# XBee4.net
KiCad netlist of a schematic drawn in EAGLE
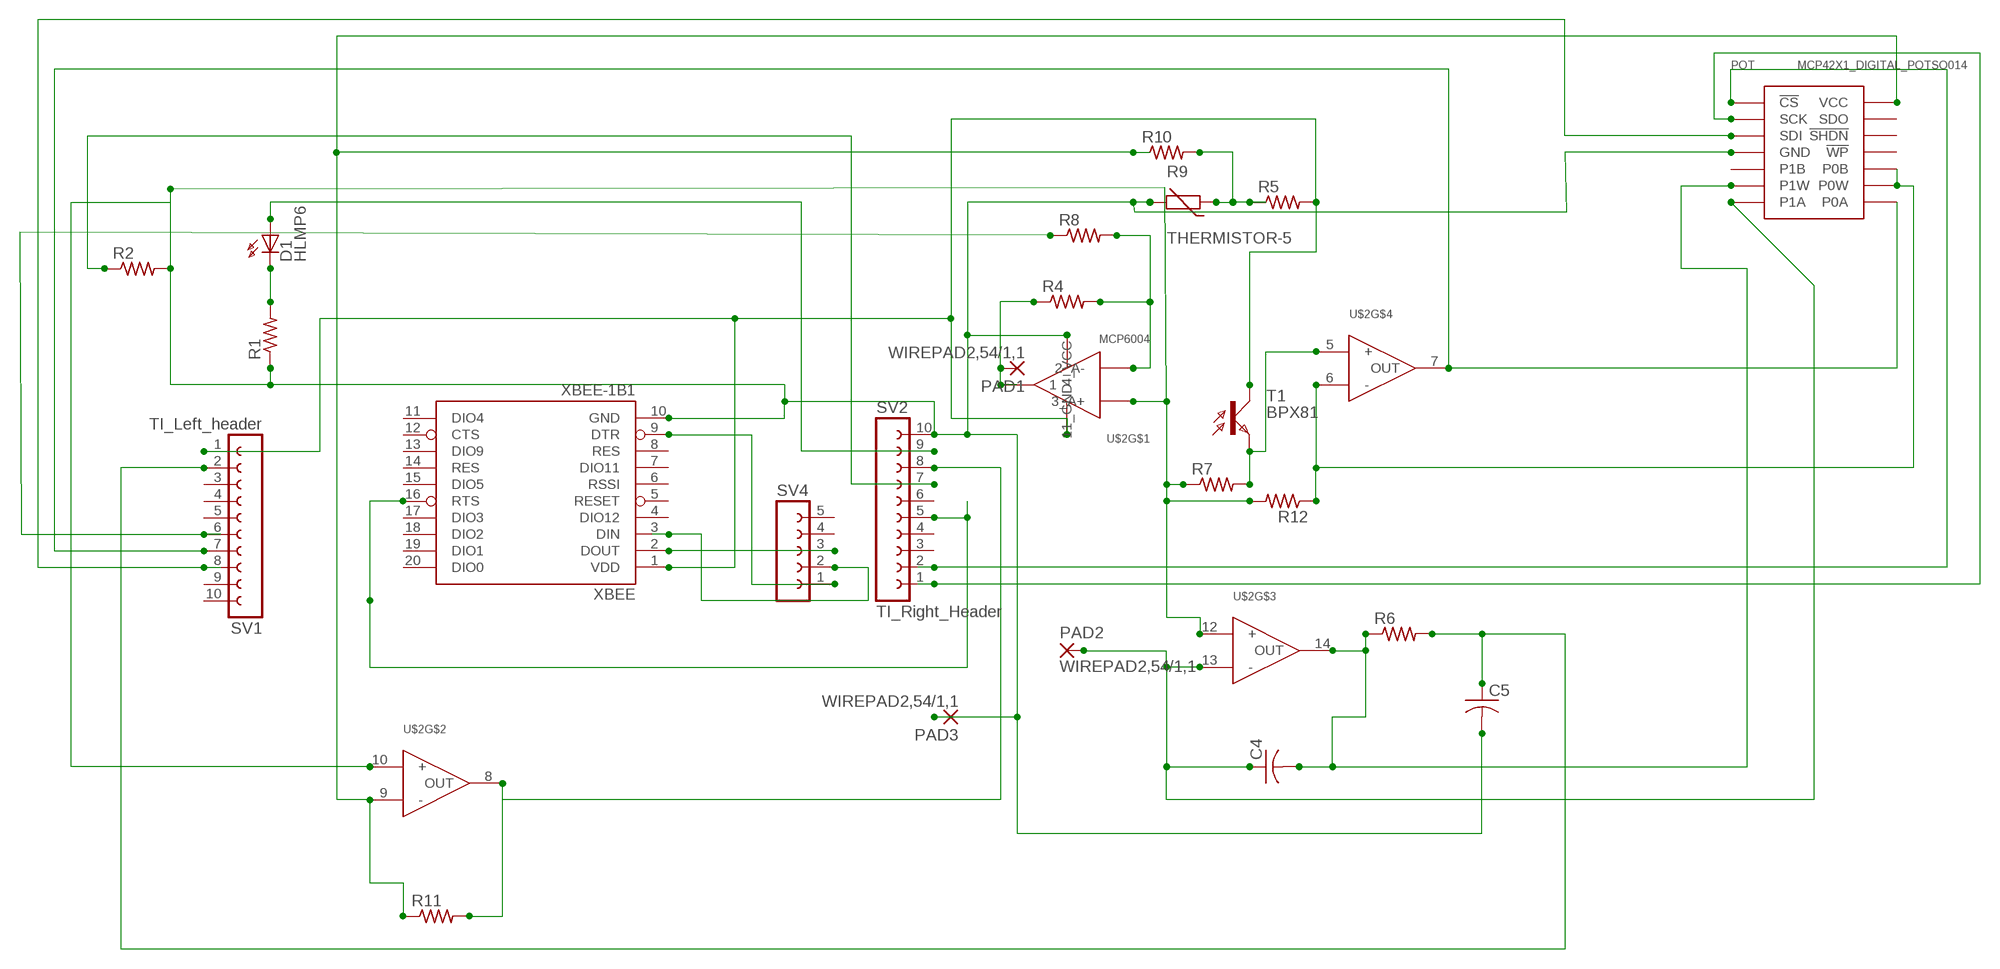
[diagram p0: schematic, sheet 1]

(export (version "E")
  (design (tool "Eeschema 10.0.6"))
  (components
    (comp (ref "C4")
      (value "C-USC0603")
      (footprint "eagle-import:C0603")
      (libsource (lib "eagle-import") (part "C-USC0603"))
    )
    (comp (ref "C5")
      (value "C-USC0603")
      (footprint "eagle-import:C0603")
      (libsource (lib "eagle-import") (part "C-USC0603"))
    )
    (comp (ref "D1")
      (value "HLMP6")
      (footprint "eagle-import:HLMP6")
      (fields (field (name "MF") "AGILENT TECHNOLOGIES") (field (name "MPN") "HLMP-6500"))
      (libsource (lib "eagle-import") (part "HLMP6"))
    )
    (comp (ref "PAD1")
      (value "WIREPAD2,54/1,1")
      (footprint "eagle-import:2,54_1,1")
      (libsource (lib "eagle-import") (part "WIREPAD2,54/1,1"))
    )
    (comp (ref "PAD2")
      (value "WIREPAD2,54/1,1")
      (footprint "eagle-import:2,54_1,1")
      (libsource (lib "eagle-import") (part "WIREPAD2,54/1,1"))
    )
    (comp (ref "PAD3")
      (value "WIREPAD2,54/1,1")
      (footprint "eagle-import:2,54_1,1")
      (libsource (lib "eagle-import") (part "WIREPAD2,54/1,1"))
    )
    (comp (ref "POT")
      (value "MCP42X1_DIGITAL_POTSO014")
      (footprint "eagle-import:SO014")
      (libsource (lib "eagle-import") (part "MCP42X1_DIGITAL_POTSO014"))
    )
    (comp (ref "R1")
      (value "R-US_R0603")
      (footprint "eagle-import:R0603")
      (libsource (lib "eagle-import") (part "R-US_R0603"))
    )
    (comp (ref "R2")
      (value "R-US_R0603")
      (footprint "eagle-import:R0603")
      (libsource (lib "eagle-import") (part "R-US_R0603"))
    )
    (comp (ref "R4")
      (value "R-US_R0603")
      (footprint "eagle-import:R0603")
      (libsource (lib "eagle-import") (part "R-US_R0603"))
    )
    (comp (ref "R5")
      (value "R-US_R0603")
      (footprint "eagle-import:R0603")
      (libsource (lib "eagle-import") (part "R-US_R0603"))
    )
    (comp (ref "R6")
      (value "R-US_R0603")
      (footprint "eagle-import:R0603")
      (libsource (lib "eagle-import") (part "R-US_R0603"))
    )
    (comp (ref "R7")
      (value "R-US_R0603")
      (footprint "eagle-import:R0603")
      (libsource (lib "eagle-import") (part "R-US_R0603"))
    )
    (comp (ref "R8")
      (value "R-US_R0603")
      (footprint "eagle-import:R0603")
      (libsource (lib "eagle-import") (part "R-US_R0603"))
    )
    (comp (ref "R9")
      (value "THERMISTOR-5")
      (footprint "eagle-import:R-5")
      (libsource (lib "eagle-import") (part "THERMISTOR-5"))
    )
    (comp (ref "R10")
      (value "R-US_R0603")
      (footprint "eagle-import:R0603")
      (libsource (lib "eagle-import") (part "R-US_R0603"))
    )
    (comp (ref "R11")
      (value "R-US_R0603")
      (footprint "eagle-import:R0603")
      (libsource (lib "eagle-import") (part "R-US_R0603"))
    )
    (comp (ref "R12")
      (value "R-US_R0603")
      (footprint "eagle-import:R0603")
      (libsource (lib "eagle-import") (part "R-US_R0603"))
    )
    (comp (ref "SV1")
      (value "TI_Left_header")
      (footprint "eagle-import:FE10")
      (libsource (lib "eagle-import") (part "FE10-1"))
    )
    (comp (ref "SV2")
      (value "TI_Right_Header")
      (footprint "eagle-import:FE10")
      (libsource (lib "eagle-import") (part "FE10-1"))
    )
    (comp (ref "SV4")
      (value "FE05-1")
      (footprint "eagle-import:FE05-1")
      (libsource (lib "eagle-import") (part "FE05-1"))
    )
    (comp (ref "T1")
      (value "BPX81")
      (footprint "eagle-import:BPX81")
      (libsource (lib "eagle-import") (part "BPX81"))
    )
    (comp (ref "U$2")
      (value "MCP6004")
      (footprint "eagle-import:SO014")
      (libsource (lib "eagle-import") (part "MCP6004"))
    )
    (comp (ref "XBEE")
      (value "XBEE-1B1")
      (footprint "eagle-import:XBEE-1")
      (libsource (lib "eagle-import") (part "XBEE-1B1"))
    )
  )
  (nets
    (net (code "1") (name "Net-(C5-Pad1)") (class "Default")
      (node (ref "C5") (pin "1") (pinfunction "1_1") (pintype "passive"))
      (node (ref "R6") (pin "2") (pinfunction "2_2") (pintype "passive"))
      (node (ref "SV1") (pin "2") (pinfunction "2_2") (pintype "passive"))
    )
    (net (code "2") (name "Net-(D1-PadA)") (class "Default")
      (node (ref "D1") (pin "A") (pinfunction "A_A") (pintype "passive"))
      (node (ref "SV2") (pin "9") (pinfunction "9_9") (pintype "passive"))
    )
    (net (code "3") (name "Net-(D1-PadK)") (class "Default")
      (node (ref "D1") (pin "K") (pinfunction "K_K") (pintype "passive"))
      (node (ref "R1") (pin "2") (pinfunction "2_2") (pintype "passive"))
    )
    (net (code "4") (name "Net-(PAD1-P)") (class "Default")
      (node (ref "PAD1") (pin "1") (pinfunction "P_1") (pintype "passive"))
      (node (ref "R4") (pin "1") (pinfunction "1_1") (pintype "passive"))
      (node (ref "U$2") (pin "1") (pinfunction "1_1") (pintype "bidirectional"))
    )
    (net (code "5") (name "Net-(PAD2-P)") (class "Default")
      (node (ref "C4") (pin "1") (pinfunction "1_1") (pintype "passive"))
      (node (ref "PAD2") (pin "1") (pinfunction "P_1") (pintype "passive"))
      (node (ref "POT") (pin "P7") (pinfunction "P1A_P7") (pintype "bidirectional"))
      (node (ref "U$2") (pin "13") (pinfunction "-_13") (pintype "bidirectional"))
    )
    (net (code "6") (name "Net-(PAD3-P)") (class "Default")
      (node (ref "C5") (pin "2") (pinfunction "2_2") (pintype "passive"))
      (node (ref "PAD3") (pin "1") (pinfunction "P_1") (pintype "passive"))
      (node (ref "POT") (pin "P4") (pinfunction "GND_P4") (pintype "bidirectional"))
      (node (ref "R1") (pin "1") (pinfunction "1_1") (pintype "passive"))
      (node (ref "R12") (pin "2") (pinfunction "2_2") (pintype "passive"))
      (node (ref "R2") (pin "2") (pinfunction "2_2") (pintype "passive"))
      (node (ref "R7") (pin "1") (pinfunction "1_1") (pintype "passive"))
      (node (ref "R9") (pin "2") (pinfunction "2_2") (pintype "passive"))
      (node (ref "SV2") (pin "10") (pinfunction "10_10") (pintype "passive"))
      (node (ref "U$2") (pin "10") (pinfunction "+_10") (pintype "bidirectional"))
      (node (ref "U$2") (pin "11") (pinfunction "11_GND_11") (pintype "power_in"))
      (node (ref "U$2") (pin "12") (pinfunction "+_12") (pintype "bidirectional"))
      (node (ref "U$2") (pin "3") (pinfunction "3_A+_3") (pintype "bidirectional"))
      (node (ref "XBEE") (pin "10") (pinfunction "GND_10") (pintype "power_in"))
    )
    (net (code "7") (name "Net-(POT-P0A)") (class "Default")
      (node (ref "POT") (pin "P8") (pinfunction "P0A_P8") (pintype "bidirectional"))
      (node (ref "SV1") (pin "7") (pinfunction "7_7") (pintype "passive"))
      (node (ref "U$2") (pin "7") (pinfunction "OUT_7") (pintype "bidirectional"))
    )
    (net (code "8") (name "Net-(POT-P0B)") (class "Default")
      (node (ref "POT") (pin "P10") (pinfunction "P0B_P10") (pintype "bidirectional"))
      (node (ref "POT") (pin "P9") (pinfunction "P0W_P9") (pintype "bidirectional"))
      (node (ref "R12") (pin "1") (pinfunction "1_1") (pintype "passive"))
      (node (ref "U$2") (pin "6") (pinfunction "-_6") (pintype "bidirectional"))
    )
    (net (code "9") (name "Net-(POT-P1W)") (class "Default")
      (node (ref "C4") (pin "2") (pinfunction "2_2") (pintype "passive"))
      (node (ref "POT") (pin "P6") (pinfunction "P1W_P6") (pintype "bidirectional"))
      (node (ref "R6") (pin "1") (pinfunction "1_1") (pintype "passive"))
      (node (ref "U$2") (pin "14") (pinfunction "OUT_14") (pintype "bidirectional"))
    )
    (net (code "10") (name "Net-(POT-SCK)") (class "Default")
      (node (ref "POT") (pin "P2") (pinfunction "SCK_P2") (pintype "bidirectional"))
      (node (ref "SV2") (pin "1") (pinfunction "1_1") (pintype "passive"))
    )
    (net (code "11") (name "Net-(POT-SDI)") (class "Default")
      (node (ref "POT") (pin "P3") (pinfunction "SDI_P3") (pintype "bidirectional"))
      (node (ref "SV1") (pin "8") (pinfunction "8_8") (pintype "passive"))
    )
    (net (code "12") (name "Net-(POT-VCC)") (class "Default")
      (node (ref "POT") (pin "P14") (pinfunction "VCC_P14") (pintype "bidirectional"))
      (node (ref "R10") (pin "1") (pinfunction "1_1") (pintype "passive"))
      (node (ref "R11") (pin "1") (pinfunction "1_1") (pintype "passive"))
      (node (ref "U$2") (pin "9") (pinfunction "-_9") (pintype "bidirectional"))
    )
    (net (code "13") (name "Net-(POT-~{CS})") (class "Default")
      (node (ref "POT") (pin "P1") (pinfunction "~{CS}_P1") (pintype "bidirectional"))
      (node (ref "SV2") (pin "2") (pinfunction "2_2") (pintype "passive"))
    )
    (net (code "14") (name "Net-(R2-Pad1)") (class "Default")
      (node (ref "R2") (pin "1") (pinfunction "1_1") (pintype "passive"))
      (node (ref "SV2") (pin "7") (pinfunction "7_7") (pintype "passive"))
    )
    (net (code "15") (name "Net-(R8-Pad1)") (class "Default")
      (node (ref "R8") (pin "1") (pinfunction "1_1") (pintype "passive"))
      (node (ref "SV1") (pin "6") (pinfunction "6_6") (pintype "passive"))
    )
    (net (code "16") (name "Net-(R10-Pad2)") (class "Default")
      (node (ref "R10") (pin "2") (pinfunction "2_2") (pintype "passive"))
      (node (ref "R5") (pin "1") (pinfunction "1_1") (pintype "passive"))
      (node (ref "R9") (pin "1") (pinfunction "1_1") (pintype "passive"))
    )
    (net (code "17") (name "Net-(U$2A-2_A-)") (class "Default")
      (node (ref "R4") (pin "2") (pinfunction "2_2") (pintype "passive"))
      (node (ref "R8") (pin "2") (pinfunction "2_2") (pintype "passive"))
      (node (ref "U$2") (pin "2") (pinfunction "2_A-_2") (pintype "bidirectional"))
    )
    (net (code "18") (name "Net-(U$2A-4_VCC)") (class "Default")
      (node (ref "R5") (pin "2") (pinfunction "2_2") (pintype "passive"))
      (node (ref "SV1") (pin "1") (pinfunction "1_1") (pintype "passive"))
      (node (ref "T1") (pin "C") (pinfunction "C_C") (pintype "passive"))
      (node (ref "U$2") (pin "4") (pinfunction "4_VCC_4") (pintype "power_in"))
      (node (ref "XBEE") (pin "1") (pinfunction "VDD_1") (pintype "power_in"))
    )
    (net (code "19") (name "Net-(U$2B-OUT)") (class "Default")
      (node (ref "R11") (pin "2") (pinfunction "2_2") (pintype "passive"))
      (node (ref "SV2") (pin "8") (pinfunction "8_8") (pintype "passive"))
      (node (ref "U$2") (pin "8") (pinfunction "OUT_8") (pintype "bidirectional"))
    )
    (net (code "20") (name "Net-(U$2D-+)") (class "Default")
      (node (ref "R7") (pin "2") (pinfunction "2_2") (pintype "passive"))
      (node (ref "T1") (pin "E") (pinfunction "E_E") (pintype "passive"))
      (node (ref "U$2") (pin "5") (pinfunction "+_5") (pintype "bidirectional"))
    )
    (net (code "21") (name "Net-(XBEE-DIN)") (class "Default")
      (node (ref "SV4") (pin "2") (pinfunction "2_2") (pintype "passive"))
      (node (ref "XBEE") (pin "3") (pinfunction "DIN_3") (pintype "input"))
    )
    (net (code "22") (name "Net-(XBEE-DOUT)") (class "Default")
      (node (ref "SV4") (pin "3") (pinfunction "3_3") (pintype "passive"))
      (node (ref "XBEE") (pin "2") (pinfunction "DOUT_2") (pintype "output"))
    )
    (net (code "23") (name "Net-(XBEE-DTR)") (class "Default")
      (node (ref "SV4") (pin "1") (pinfunction "1_1") (pintype "passive"))
      (node (ref "XBEE") (pin "9") (pinfunction "DTR_9") (pintype "bidirectional"))
    )
    (net (code "24") (name "Net-(XBEE-RTS)") (class "Default")
      (node (ref "SV2") (pin "5") (pinfunction "5_5") (pintype "passive"))
      (node (ref "XBEE") (pin "16") (pinfunction "RTS_16") (pintype "input"))
    )
    (net (code "25") (name "unconnected-(POT-P1B-PadP5)") (class "Default")
      (node (ref "POT") (pin "P5") (pinfunction "P1B_P5") (pintype "bidirectional"))
    )
    (net (code "26") (name "unconnected-(POT-SDO-PadP13)") (class "Default")
      (node (ref "POT") (pin "P13") (pinfunction "SDO_P13") (pintype "bidirectional"))
    )
    (net (code "27") (name "unconnected-(POT-~{SHDN}-PadP12)") (class "Default")
      (node (ref "POT") (pin "P12") (pinfunction "~{SHDN}_P12") (pintype "bidirectional"))
    )
    (net (code "28") (name "unconnected-(POT-~{WP}-PadP11)") (class "Default")
      (node (ref "POT") (pin "P11") (pinfunction "~{WP}_P11") (pintype "bidirectional"))
    )
    (net (code "29") (name "unconnected-(SV1-Pad3)") (class "Default")
      (node (ref "SV1") (pin "3") (pinfunction "3_3") (pintype "passive"))
    )
    (net (code "30") (name "unconnected-(SV1-Pad4)") (class "Default")
      (node (ref "SV1") (pin "4") (pinfunction "4_4") (pintype "passive"))
    )
    (net (code "31") (name "unconnected-(SV1-Pad5)") (class "Default")
      (node (ref "SV1") (pin "5") (pinfunction "5_5") (pintype "passive"))
    )
    (net (code "32") (name "unconnected-(SV1-Pad9)") (class "Default")
      (node (ref "SV1") (pin "9") (pinfunction "9_9") (pintype "passive"))
    )
    (net (code "33") (name "unconnected-(SV1-Pad10)") (class "Default")
      (node (ref "SV1") (pin "10") (pinfunction "10_10") (pintype "passive"))
    )
    (net (code "34") (name "unconnected-(SV2-Pad3)") (class "Default")
      (node (ref "SV2") (pin "3") (pinfunction "3_3") (pintype "passive"))
    )
    (net (code "35") (name "unconnected-(SV2-Pad4)") (class "Default")
      (node (ref "SV2") (pin "4") (pinfunction "4_4") (pintype "passive"))
    )
    (net (code "36") (name "unconnected-(SV2-Pad6)") (class "Default")
      (node (ref "SV2") (pin "6") (pinfunction "6_6") (pintype "passive"))
    )
    (net (code "37") (name "unconnected-(SV4-Pad4)") (class "Default")
      (node (ref "SV4") (pin "4") (pinfunction "4_4") (pintype "passive"))
    )
    (net (code "38") (name "unconnected-(SV4-Pad5)") (class "Default")
      (node (ref "SV4") (pin "5") (pinfunction "5_5") (pintype "passive"))
    )
    (net (code "39") (name "unconnected-(XBEE-CTS-Pad12)") (class "Default")
      (node (ref "XBEE") (pin "12") (pinfunction "CTS_12") (pintype "output"))
    )
    (net (code "40") (name "unconnected-(XBEE-DIO0-Pad20)") (class "Default")
      (node (ref "XBEE") (pin "20") (pinfunction "DIO0_20") (pintype "bidirectional"))
    )
    (net (code "41") (name "unconnected-(XBEE-DIO1-Pad19)") (class "Default")
      (node (ref "XBEE") (pin "19") (pinfunction "DIO1_19") (pintype "bidirectional"))
    )
    (net (code "42") (name "unconnected-(XBEE-DIO2-Pad18)") (class "Default")
      (node (ref "XBEE") (pin "18") (pinfunction "DIO2_18") (pintype "bidirectional"))
    )
    (net (code "43") (name "unconnected-(XBEE-DIO3-Pad17)") (class "Default")
      (node (ref "XBEE") (pin "17") (pinfunction "DIO3_17") (pintype "bidirectional"))
    )
    (net (code "44") (name "unconnected-(XBEE-DIO4-Pad11)") (class "Default")
      (node (ref "XBEE") (pin "11") (pinfunction "DIO4_11") (pintype "bidirectional"))
    )
    (net (code "45") (name "unconnected-(XBEE-DIO5-Pad15)") (class "Default")
      (node (ref "XBEE") (pin "15") (pinfunction "DIO5_15") (pintype "bidirectional"))
    )
    (net (code "46") (name "unconnected-(XBEE-DIO9-Pad13)") (class "Default")
      (node (ref "XBEE") (pin "13") (pinfunction "DIO9_13") (pintype "bidirectional"))
    )
    (net (code "47") (name "unconnected-(XBEE-DIO11-Pad7)") (class "Default")
      (node (ref "XBEE") (pin "7") (pinfunction "DIO11_7") (pintype "bidirectional"))
    )
    (net (code "48") (name "unconnected-(XBEE-DIO12-Pad4)") (class "Default")
      (node (ref "XBEE") (pin "4") (pinfunction "DIO12_4") (pintype "bidirectional"))
    )
    (net (code "49") (name "unconnected-(XBEE-RES-Pad8)") (class "Default")
      (node (ref "XBEE") (pin "8") (pinfunction "RES_8") (pintype "bidirectional"))
    )
    (net (code "50") (name "unconnected-(XBEE-RES-Pad14)") (class "Default")
      (node (ref "XBEE") (pin "14") (pinfunction "RES_14") (pintype "bidirectional"))
    )
    (net (code "51") (name "unconnected-(XBEE-RESET-Pad5)") (class "Default")
      (node (ref "XBEE") (pin "5") (pinfunction "RESET_5") (pintype "input"))
    )
    (net (code "52") (name "unconnected-(XBEE-RSSI-Pad6)") (class "Default")
      (node (ref "XBEE") (pin "6") (pinfunction "RSSI_6") (pintype "bidirectional"))
    )
  )
)
